# SERVO_UNIT.net
KiCad netlist of a schematic drawn in EAGLE
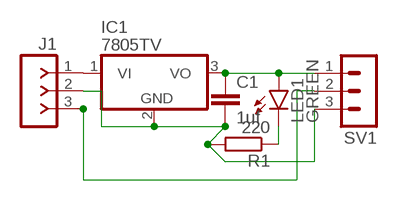
[diagram p0: schematic, sheet 1]

(export (version "E")
  (design (tool "Eeschema 10.0.6"))
  (components
    (comp (ref "C1")
      (value "1uf")
      (footprint "eagle-import:C025-025X050")
      (libsource (lib "eagle-import") (part "C-EU025-025X050"))
    )
    (comp (ref "IC1")
      (value "7805TV")
      (footprint "eagle-import:TO220V")
      (libsource (lib "eagle-import") (part "78TV05"))
    )
    (comp (ref "J1")
      (value "F-1X03-SIP-100-32Y")
      (footprint "eagle-import:SIP-100-03-32Y")
      (libsource (lib "eagle-import") (part "F-1X03-SIP-100-32Y"))
    )
    (comp (ref "LED1")
      (value "GREEN")
      (footprint "eagle-import:SML0805")
      (libsource (lib "eagle-import") (part "LEDSML0805"))
    )
    (comp (ref "R1")
      (value "220")
      (footprint "eagle-import:0204_7")
      (libsource (lib "eagle-import") (part "R-EU_0204/7"))
    )
    (comp (ref "SV1")
      (value "MA03-1")
      (footprint "eagle-import:MA03-1")
      (libsource (lib "eagle-import") (part "MA03-1"))
    )
  )
  (nets
    (net (code "1") (name "Net-(IC1-GND)") (class "Default")
      (node (ref "C1") (pin "2") (pinfunction "2_2") (pintype "passive"))
      (node (ref "IC1") (pin "2") (pinfunction "GND_2") (pintype "passive"))
      (node (ref "J1") (pin "2") (pinfunction "2_2") (pintype "passive"))
      (node (ref "R1") (pin "2") (pinfunction "2_2") (pintype "passive"))
      (node (ref "SV1") (pin "3") (pinfunction "3_3") (pintype "passive"))
    )
    (net (code "2") (name "Net-(IC1-VI)") (class "Default")
      (node (ref "IC1") (pin "1") (pinfunction "VI_1") (pintype "input"))
      (node (ref "J1") (pin "1") (pinfunction "1_1") (pintype "passive"))
    )
    (net (code "3") (name "Net-(IC1-VO)") (class "Default")
      (node (ref "C1") (pin "1") (pinfunction "1_1") (pintype "passive"))
      (node (ref "IC1") (pin "3") (pinfunction "VO_3") (pintype "passive"))
      (node (ref "LED1") (pin "A") (pinfunction "A_A") (pintype "passive"))
      (node (ref "SV1") (pin "1") (pinfunction "1_1") (pintype "passive"))
    )
    (net (code "4") (name "Net-(J1-Pad3)") (class "Default")
      (node (ref "J1") (pin "3") (pinfunction "3_3") (pintype "passive"))
      (node (ref "SV1") (pin "2") (pinfunction "2_2") (pintype "passive"))
    )
    (net (code "5") (name "Net-(LED1-PadC)") (class "Default")
      (node (ref "LED1") (pin "C") (pinfunction "C_C") (pintype "passive"))
      (node (ref "R1") (pin "1") (pinfunction "1_1") (pintype "passive"))
    )
  )
)
